# USB_Power_Adapter.net
KiCad netlist of a schematic drawn in EAGLE
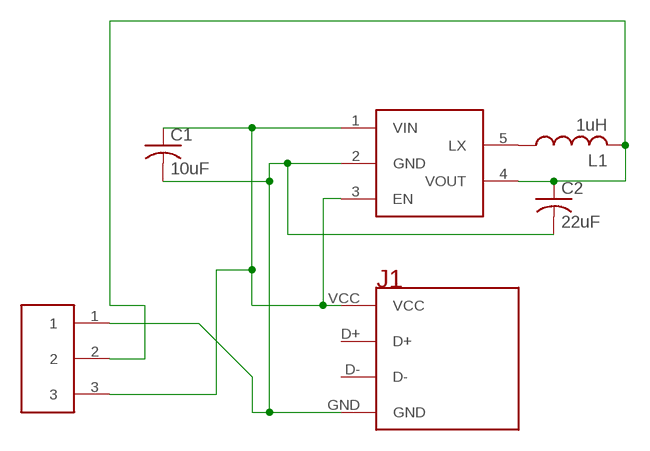
[diagram p0: schematic, sheet 1]

(export (version "E")
  (design (tool "Eeschema 10.0.6"))
  (components
    (comp (ref "C1")
      (value "10uF")
      (footprint "eagle-import:C0805K")
      (libsource (lib "eagle-import") (part "C-USC0805K"))
    )
    (comp (ref "C2")
      (value "22uF")
      (footprint "eagle-import:C0805K")
      (libsource (lib "eagle-import") (part "C-USC0805K"))
    )
    (comp (ref "J1")
      (value "MICROUSBMICROUSB_THRU")
      (footprint "eagle-import:MICROUSB_THRU")
      (libsource (lib "eagle-import") (part "MICROUSBMICROUSB_THRU"))
    )
    (comp (ref "L1")
      (value "1uH")
      (footprint "eagle-import:L3225M")
      (libsource (lib "eagle-import") (part "L-USL3225M"))
    )
    (comp (ref "U$2")
      (value "DF3_1X3")
      (footprint "eagle-import:DF3_1X3")
      (libsource (lib "eagle-import") (part "DF3_1X3"))
    )
    (comp (ref "U1")
      (value "SC189")
      (footprint "eagle-import:SC189")
      (libsource (lib "eagle-import") (part "SC189"))
    )
  )
  (nets
    (net (code "1") (name "Net-(U1-EN)") (class "Default")
      (node (ref "C1") (pin "1") (pinfunction "1_1") (pintype "passive"))
      (node (ref "J1") (pin "VCC") (pinfunction "VCC_VCC") (pintype "bidirectional"))
      (node (ref "U$2") (pin "3") (pinfunction "3_3") (pintype "bidirectional"))
      (node (ref "U1") (pin "1") (pinfunction "VIN_1") (pintype "bidirectional"))
      (node (ref "U1") (pin "3") (pinfunction "EN_3") (pintype "bidirectional"))
    )
    (net (code "2") (name "Net-(U1-GND)") (class "Default")
      (node (ref "C1") (pin "2") (pinfunction "2_2") (pintype "passive"))
      (node (ref "C2") (pin "2") (pinfunction "2_2") (pintype "passive"))
      (node (ref "J1") (pin "GND") (pinfunction "GND_GND") (pintype "bidirectional"))
      (node (ref "U$2") (pin "1") (pinfunction "1_1") (pintype "bidirectional"))
      (node (ref "U1") (pin "2") (pinfunction "GND_2") (pintype "bidirectional"))
    )
    (net (code "3") (name "Net-(U1-LX)") (class "Default")
      (node (ref "L1") (pin "1") (pinfunction "1_1") (pintype "passive"))
      (node (ref "U1") (pin "5") (pinfunction "LX_5") (pintype "bidirectional"))
    )
    (net (code "4") (name "Net-(U1-VOUT)") (class "Default")
      (node (ref "C2") (pin "1") (pinfunction "1_1") (pintype "passive"))
      (node (ref "L1") (pin "2") (pinfunction "2_2") (pintype "passive"))
      (node (ref "U$2") (pin "2") (pinfunction "2_2") (pintype "bidirectional"))
      (node (ref "U1") (pin "4") (pinfunction "VOUT_4") (pintype "bidirectional"))
    )
    (net (code "5") (name "unconnected-(J1-PadD+)") (class "Default")
      (node (ref "J1") (pin "D+") (pinfunction "D+_D+") (pintype "bidirectional"))
    )
    (net (code "6") (name "unconnected-(J1-PadD-)") (class "Default")
      (node (ref "J1") (pin "D-") (pinfunction "D-_D-") (pintype "bidirectional"))
    )
  )
)
